# ir_remote.net
KiCad netlist of a schematic drawn in EAGLE
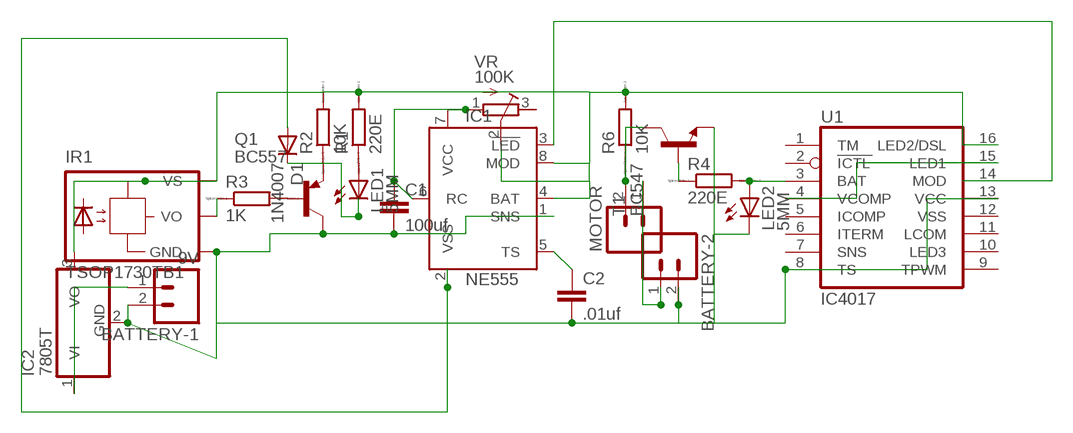
[diagram p0: schematic, sheet 1]

(export (version "E")
  (design (tool "Eeschema 10.0.6"))
  (components
    (comp (ref "BATTERY-1")
      (value "9V")
      (footprint "eagle-import:02P")
      (libsource (lib "eagle-import") (part "M02"))
    )
    (comp (ref "BATTERY-2")
      (value "M02")
      (footprint "eagle-import:02P")
      (libsource (lib "eagle-import") (part "M02"))
    )
    (comp (ref "C1")
      (value "100uf")
      (footprint "eagle-import:C5B7.2")
      (libsource (lib "eagle-import") (part "C5/7.2"))
    )
    (comp (ref "C2")
      (value ".01uf")
      (footprint "eagle-import:C2.5-3")
      (libsource (lib "eagle-import") (part "C2,5-3"))
    )
    (comp (ref "D1")
      (value "1N4007")
      (footprint "eagle-import:DO41-10")
      (libsource (lib "eagle-import") (part "1N4004"))
    )
    (comp (ref "IC1")
      (value "NE555")
      (footprint "eagle-import:DIL08")
      (fields (field (name "MF") "TEXAS INSTRUMENT CONNECTORS") (field (name "MPN") "BQ2000TPN-B5"))
      (libsource (lib "eagle-import") (part "BQ2000TPN"))
    )
    (comp (ref "IC2")
      (value "7805T")
      (footprint "eagle-import:TO220H")
      (libsource (lib "eagle-import") (part "78T05"))
    )
    (comp (ref "IR1")
      (value "TSOP1730TB1")
      (footprint "eagle-import:TSOP17_TB1")
      (libsource (lib "eagle-import") (part "TSOP17TB130"))
    )
    (comp (ref "LED1")
      (value "5MM")
      (footprint "eagle-import:LED5MM")
      (libsource (lib "eagle-import") (part "LED5MM"))
    )
    (comp (ref "LED2")
      (value "5MM")
      (footprint "eagle-import:LED5MM")
      (libsource (lib "eagle-import") (part "LED5MM"))
    )
    (comp (ref "MOTOR")
      (value "M02")
      (footprint "eagle-import:02P")
      (libsource (lib "eagle-import") (part "M02"))
    )
    (comp (ref "Q1")
      (value "BC557")
      (footprint "eagle-import:TO92")
      (libsource (lib "eagle-import") (part "BC557"))
    )
    (comp (ref "R1")
      (value "220E")
      (footprint "eagle-import:0204_7")
      (libsource (lib "eagle-import") (part "R0204/7"))
    )
    (comp (ref "R2")
      (value "10K")
      (footprint "eagle-import:0204_7")
      (libsource (lib "eagle-import") (part "R0204/7"))
    )
    (comp (ref "R3")
      (value "1K")
      (footprint "eagle-import:0204_7")
      (libsource (lib "eagle-import") (part "R0204/7"))
    )
    (comp (ref "R4")
      (value "220E")
      (footprint "eagle-import:0204_7")
      (libsource (lib "eagle-import") (part "R0204/7"))
    )
    (comp (ref "R6")
      (value "10K")
      (footprint "eagle-import:0204_7")
      (libsource (lib "eagle-import") (part "R0204/7"))
    )
    (comp (ref "T1")
      (value "BC547")
      (footprint "eagle-import:TO92")
      (libsource (lib "eagle-import") (part "BC547"))
    )
    (comp (ref "U1")
      (value "IC4017")
      (footprint "eagle-import:DIL16")
      (fields (field (name "MF") "TEXAS INSTRUMENT CONNECTORS") (field (name "MPN") "BQ2054PN"))
      (libsource (lib "eagle-import") (part "BQ2054PN"))
    )
    (comp (ref "VR")
      (value "100K")
      (footprint "eagle-import:RTRIM64P")
      (libsource (lib "eagle-import") (part "R-TRIMM64P"))
    )
  )
  (nets
    (net (code "1") (name "/VSS") (class "Default")
      (node (ref "U1") (pin "12") (pinfunction "VSS_12") (pintype "power_in"))
    )
    (net (code "2") (name "Net-(BATTERY-2-Pad1)") (class "Default")
      (node (ref "BATTERY-2") (pin "1") (pinfunction "1_1") (pintype "passive"))
      (node (ref "MOTOR") (pin "1") (pinfunction "1_1") (pintype "passive"))
    )
    (net (code "3") (name "Net-(IC1-BAT)") (class "Default")
      (node (ref "IC1") (pin "4") (pinfunction "BAT_4") (pintype "input"))
      (node (ref "IC1") (pin "8") (pinfunction "MOD_8") (pintype "output"))
      (node (ref "IC2") (pin "3") (pinfunction "VO_3") (pintype "passive"))
      (node (ref "IR1") (pin "VS") (pinfunction "VS_VS") (pintype "power_in"))
      (node (ref "R1") (pin "2") (pinfunction "2_2") (pintype "passive"))
      (node (ref "R2") (pin "2") (pinfunction "2_2") (pintype "passive"))
      (node (ref "R6") (pin "2") (pinfunction "2_2") (pintype "passive"))
      (node (ref "U1") (pin "16") (pinfunction "LED2/DSL_16") (pintype "tri_state"))
      (node (ref "VR") (pin "2") (pinfunction "S_2") (pintype "passive"))
    )
    (net (code "4") (name "Net-(IC1-RC)") (class "Default")
      (node (ref "C1") (pin "1") (pinfunction "1_1") (pintype "passive"))
      (node (ref "IC1") (pin "6") (pinfunction "RC_6") (pintype "input"))
      (node (ref "IC1") (pin "7") (pinfunction "VCC_7") (pintype "input"))
      (node (ref "VR") (pin "1") (pinfunction "E_1") (pintype "passive"))
    )
    (net (code "5") (name "Net-(IC1-SNS)") (class "Default")
      (node (ref "BATTERY-1") (pin "2") (pinfunction "2_2") (pintype "passive"))
      (node (ref "BATTERY-2") (pin "2") (pinfunction "2_2") (pintype "passive"))
      (node (ref "C1") (pin "2") (pinfunction "2_2") (pintype "passive"))
      (node (ref "C2") (pin "2") (pinfunction "2_2") (pintype "passive"))
      (node (ref "IC1") (pin "1") (pinfunction "SNS_1") (pintype "input"))
      (node (ref "IC2") (pin "2") (pinfunction "GND_2") (pintype "passive"))
      (node (ref "IR1") (pin "GND") (pinfunction "GND_GND") (pintype "power_in"))
      (node (ref "LED2") (pin "K") (pinfunction "C_K") (pintype "passive"))
      (node (ref "Q1") (pin "3") (pinfunction "C_3") (pintype "passive"))
      (node (ref "T1") (pin "1") (pinfunction "E_1") (pintype "passive"))
      (node (ref "U1") (pin "13") (pinfunction "VCC_13") (pintype "power_in"))
      (node (ref "U1") (pin "8") (pinfunction "TS_8") (pintype "input"))
    )
    (net (code "6") (name "Net-(IC1-TS)") (class "Default")
      (node (ref "C2") (pin "1") (pinfunction "1_1") (pintype "passive"))
      (node (ref "IC1") (pin "5") (pinfunction "TS_5") (pintype "input"))
    )
    (net (code "7") (name "Net-(IC1-VSS)") (class "Default")
      (node (ref "D1") (pin "A") (pinfunction "A_A") (pintype "passive"))
      (node (ref "IC1") (pin "2") (pinfunction "VSS_2") (pintype "power_in"))
    )
    (net (code "8") (name "Net-(IC1-~{LED})") (class "Default")
      (node (ref "IC1") (pin "3") (pinfunction "~{LED}_3") (pintype "output"))
      (node (ref "U1") (pin "14") (pinfunction "MOD_14") (pintype "output"))
    )
    (net (code "9") (name "Net-(IC2-VI)") (class "Default")
      (node (ref "BATTERY-1") (pin "1") (pinfunction "1_1") (pintype "passive"))
      (node (ref "IC2") (pin "1") (pinfunction "VI_1") (pintype "input"))
    )
    (net (code "10") (name "Net-(IR1-PadVO)") (class "Default")
      (node (ref "IR1") (pin "VO") (pinfunction "VO_VO") (pintype "open_collector"))
      (node (ref "R3") (pin "1") (pinfunction "1_1") (pintype "passive"))
    )
    (net (code "11") (name "Net-(LED1-C)") (class "Default")
      (node (ref "D1") (pin "C") (pinfunction "C_C") (pintype "passive"))
      (node (ref "LED1") (pin "K") (pinfunction "C_K") (pintype "passive"))
      (node (ref "Q1") (pin "1") (pinfunction "E_1") (pintype "passive"))
      (node (ref "R2") (pin "1") (pinfunction "1_1") (pintype "passive"))
    )
    (net (code "12") (name "Net-(LED1-PadA)") (class "Default")
      (node (ref "LED1") (pin "A") (pinfunction "A_A") (pintype "passive"))
      (node (ref "R1") (pin "1") (pinfunction "1_1") (pintype "passive"))
    )
    (net (code "13") (name "Net-(Q1-B)") (class "Default")
      (node (ref "Q1") (pin "2") (pinfunction "B_2") (pintype "passive"))
      (node (ref "R3") (pin "2") (pinfunction "2_2") (pintype "passive"))
    )
    (net (code "14") (name "Net-(T1-B)") (class "Default")
      (node (ref "R4") (pin "1") (pinfunction "1_1") (pintype "passive"))
      (node (ref "T1") (pin "2") (pinfunction "B_2") (pintype "passive"))
    )
    (net (code "15") (name "Net-(T1-C)") (class "Default")
      (node (ref "MOTOR") (pin "2") (pinfunction "2_2") (pintype "passive"))
      (node (ref "R6") (pin "1") (pinfunction "1_1") (pintype "passive"))
      (node (ref "T1") (pin "3") (pinfunction "C_3") (pintype "passive"))
    )
    (net (code "16") (name "Net-(U1-BAT)") (class "Default")
      (node (ref "LED2") (pin "A") (pinfunction "A_A") (pintype "passive"))
      (node (ref "R4") (pin "2") (pinfunction "2_2") (pintype "passive"))
      (node (ref "U1") (pin "3") (pinfunction "BAT_3") (pintype "input"))
    )
    (net (code "17") (name "Net-(U1-LED1)") (class "Default")
      (node (ref "U1") (pin "15") (pinfunction "LED1_15") (pintype "tri_state"))
      (node (ref "U1") (pin "4") (pinfunction "VCOMP_4") (pintype "input"))
    )
    (net (code "18") (name "unconnected-(U1-ICOMP-Pad5)") (class "Default")
      (node (ref "U1") (pin "5") (pinfunction "ICOMP_5") (pintype "input"))
    )
    (net (code "19") (name "unconnected-(U1-ICTL-Pad2)") (class "Default")
      (node (ref "U1") (pin "2") (pinfunction "ICTL_2") (pintype "output"))
    )
    (net (code "20") (name "unconnected-(U1-ITERM-Pad6)") (class "Default")
      (node (ref "U1") (pin "6") (pinfunction "ITERM_6") (pintype "input"))
    )
    (net (code "21") (name "unconnected-(U1-LCOM-Pad11)") (class "Default")
      (node (ref "U1") (pin "11") (pinfunction "LCOM_11") (pintype "output"))
    )
    (net (code "22") (name "unconnected-(U1-LED3-Pad10)") (class "Default")
      (node (ref "U1") (pin "10") (pinfunction "LED3_10") (pintype "tri_state"))
    )
    (net (code "23") (name "unconnected-(U1-SNS-Pad7)") (class "Default")
      (node (ref "U1") (pin "7") (pinfunction "SNS_7") (pintype "input"))
    )
    (net (code "24") (name "unconnected-(U1-TM-Pad1)") (class "Default")
      (node (ref "U1") (pin "1") (pinfunction "TM_1") (pintype "input"))
    )
    (net (code "25") (name "unconnected-(U1-TPWM-Pad9)") (class "Default")
      (node (ref "U1") (pin "9") (pinfunction "TPWM_9") (pintype "input"))
    )
    (net (code "26") (name "unconnected-(VR-A-Pad3)") (class "Default")
      (node (ref "VR") (pin "3") (pinfunction "A_3") (pintype "passive"))
    )
  )
)
